# bbr18_pc_battery_connection_board.net
KiCad netlist of a schematic drawn in Altium Designer
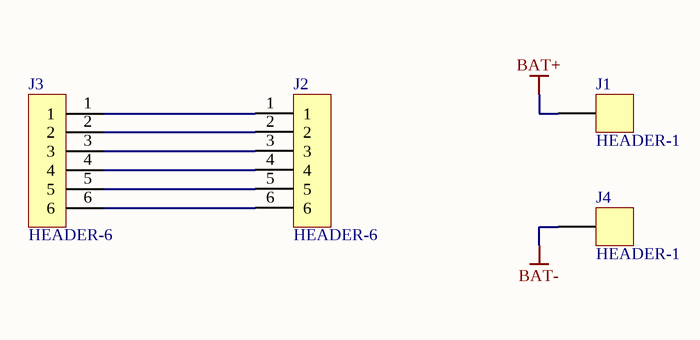
[diagram p0: bbr18_pc_battery_connection_board.SchDoc]

(export (version "E")
  (design (tool "Eeschema 10.0.6"))
  (components
    (comp (ref "J1")
      (value "HEADER-1")
      (footprint "2MM-BANANA-VIA")
      (libsource (lib "connectors") (part "HEADER-1"))
    )
    (comp (ref "J2")
      (value "HEADER-6")
      (footprint "MICRO-MATCH-FOB-06")
      (libsource (lib "connectors_micromatch") (part "HEADER-6"))
    )
    (comp (ref "J3")
      (value "HEADER-6")
      (footprint "MICRO-MATCH-FOB-06")
      (libsource (lib "") (part "HEADER-6_1"))
    )
    (comp (ref "J4")
      (value "HEADER-1")
      (footprint "2MM-BANANA-VIA")
      (libsource (lib "connectors") (part "HEADER-1"))
    )
  )
  (nets
    (net (code "1") (name "BAT+") (class "Default")
      (node (ref "J1") (pin "1") (pinfunction "1_1") (pintype "passive"))
    )
    (net (code "2") (name "BAT-") (class "Default")
      (node (ref "J4") (pin "1") (pinfunction "1_1") (pintype "passive"))
    )
    (net (code "3") (name "Net-(J2-Pad1)") (class "Default")
      (node (ref "J2") (pin "1") (pinfunction "1_1") (pintype "passive"))
      (node (ref "J3") (pin "1") (pinfunction "1_1") (pintype "passive"))
    )
    (net (code "4") (name "Net-(J2-Pad2)") (class "Default")
      (node (ref "J2") (pin "2") (pinfunction "2_2") (pintype "passive"))
      (node (ref "J3") (pin "2") (pinfunction "2_2") (pintype "passive"))
    )
    (net (code "5") (name "Net-(J2-Pad3)") (class "Default")
      (node (ref "J2") (pin "3") (pinfunction "3_3") (pintype "passive"))
      (node (ref "J3") (pin "3") (pinfunction "3_3") (pintype "passive"))
    )
    (net (code "6") (name "Net-(J2-Pad4)") (class "Default")
      (node (ref "J2") (pin "4") (pinfunction "4_4") (pintype "passive"))
      (node (ref "J3") (pin "4") (pinfunction "4_4") (pintype "passive"))
    )
    (net (code "7") (name "Net-(J2-Pad5)") (class "Default")
      (node (ref "J2") (pin "5") (pinfunction "5_5") (pintype "passive"))
      (node (ref "J3") (pin "5") (pinfunction "5_5") (pintype "passive"))
    )
    (net (code "8") (name "Net-(J2-Pad6)") (class "Default")
      (node (ref "J2") (pin "6") (pinfunction "6_6") (pintype "passive"))
      (node (ref "J3") (pin "6") (pinfunction "6_6") (pintype "passive"))
    )
  )
)
